# transformer_balancing.net
KiCad netlist of a schematic drawn in EAGLE
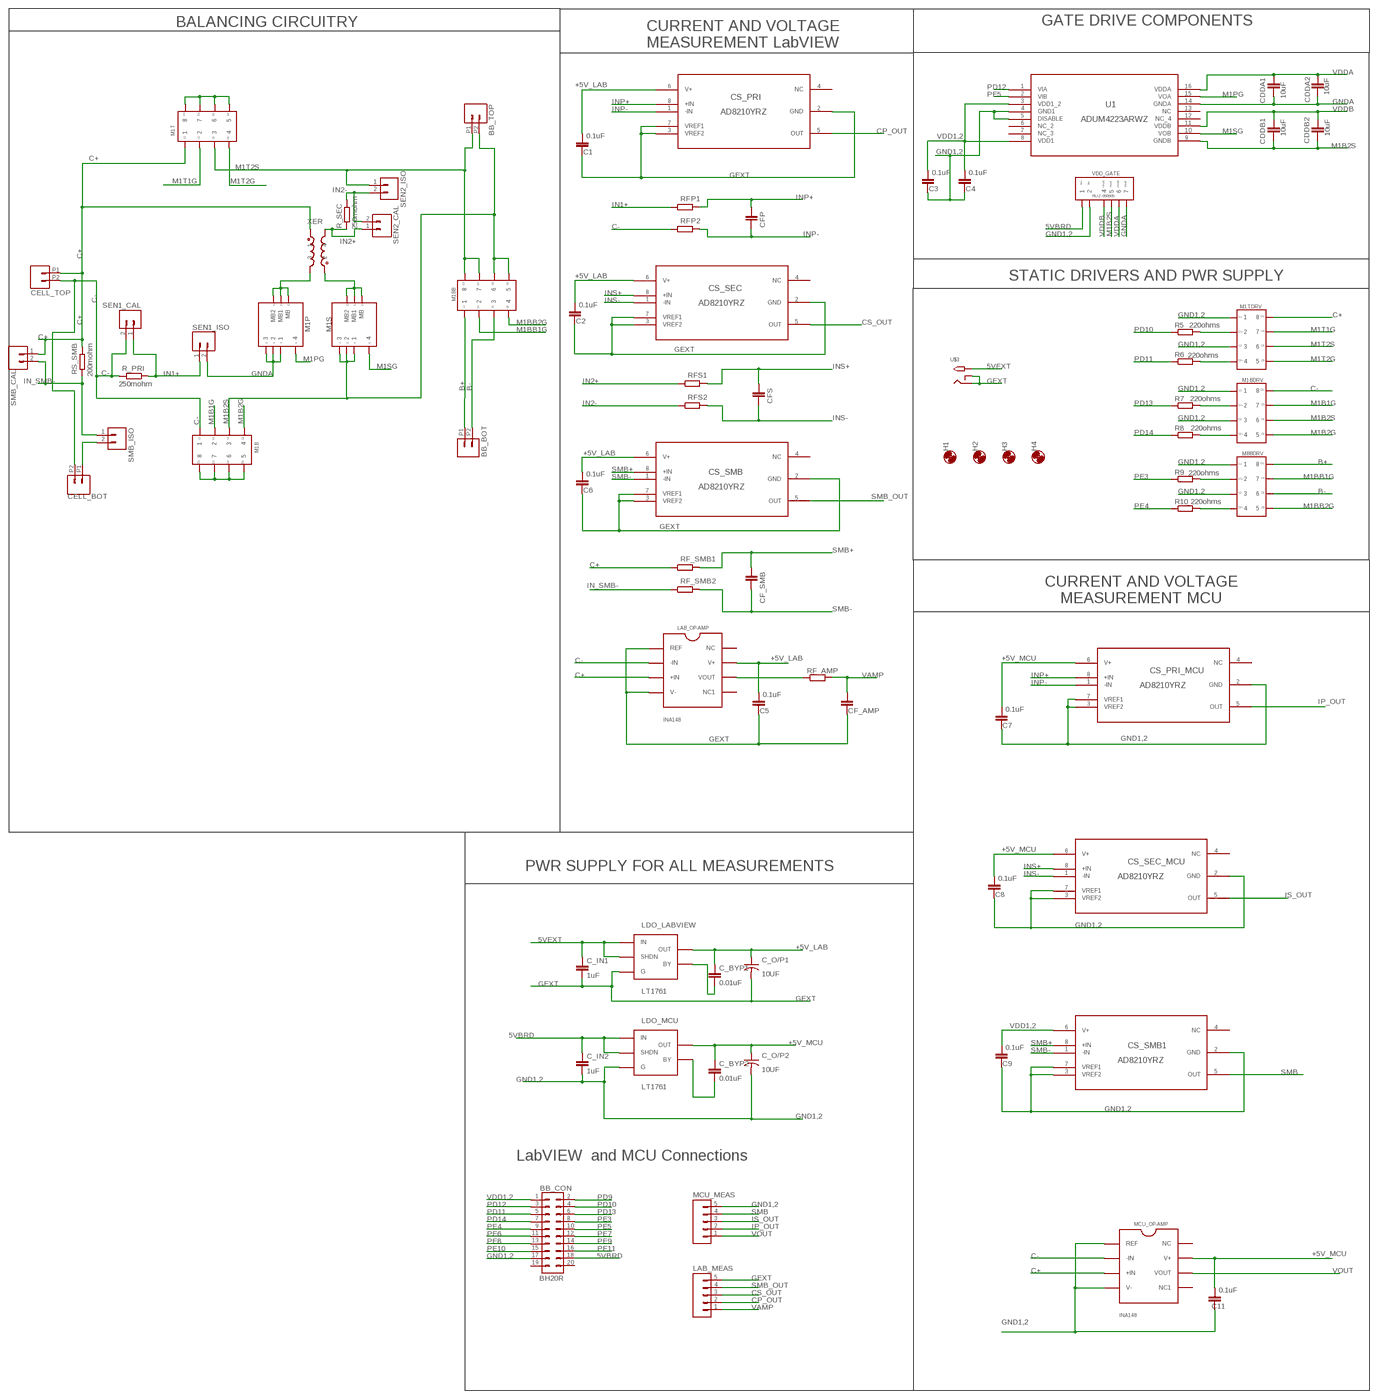
[diagram p0: schematic, sheet 1, overview]
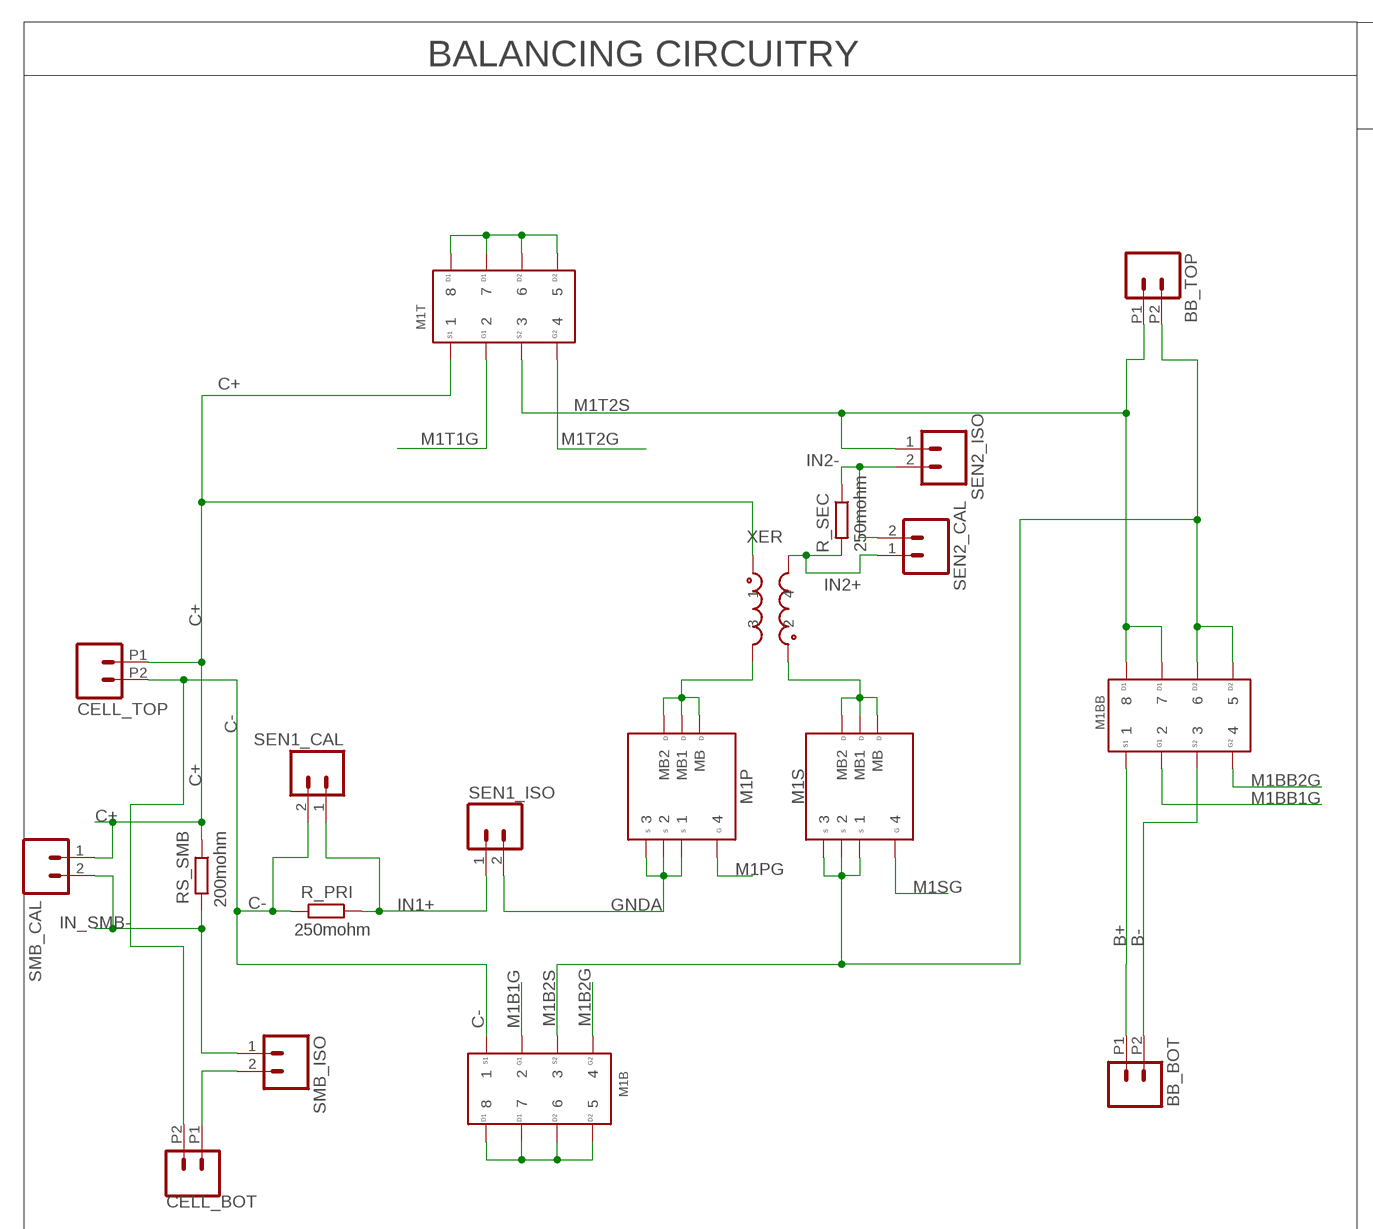
[diagram p1: schematic, sheet 1, part 1 of 4]
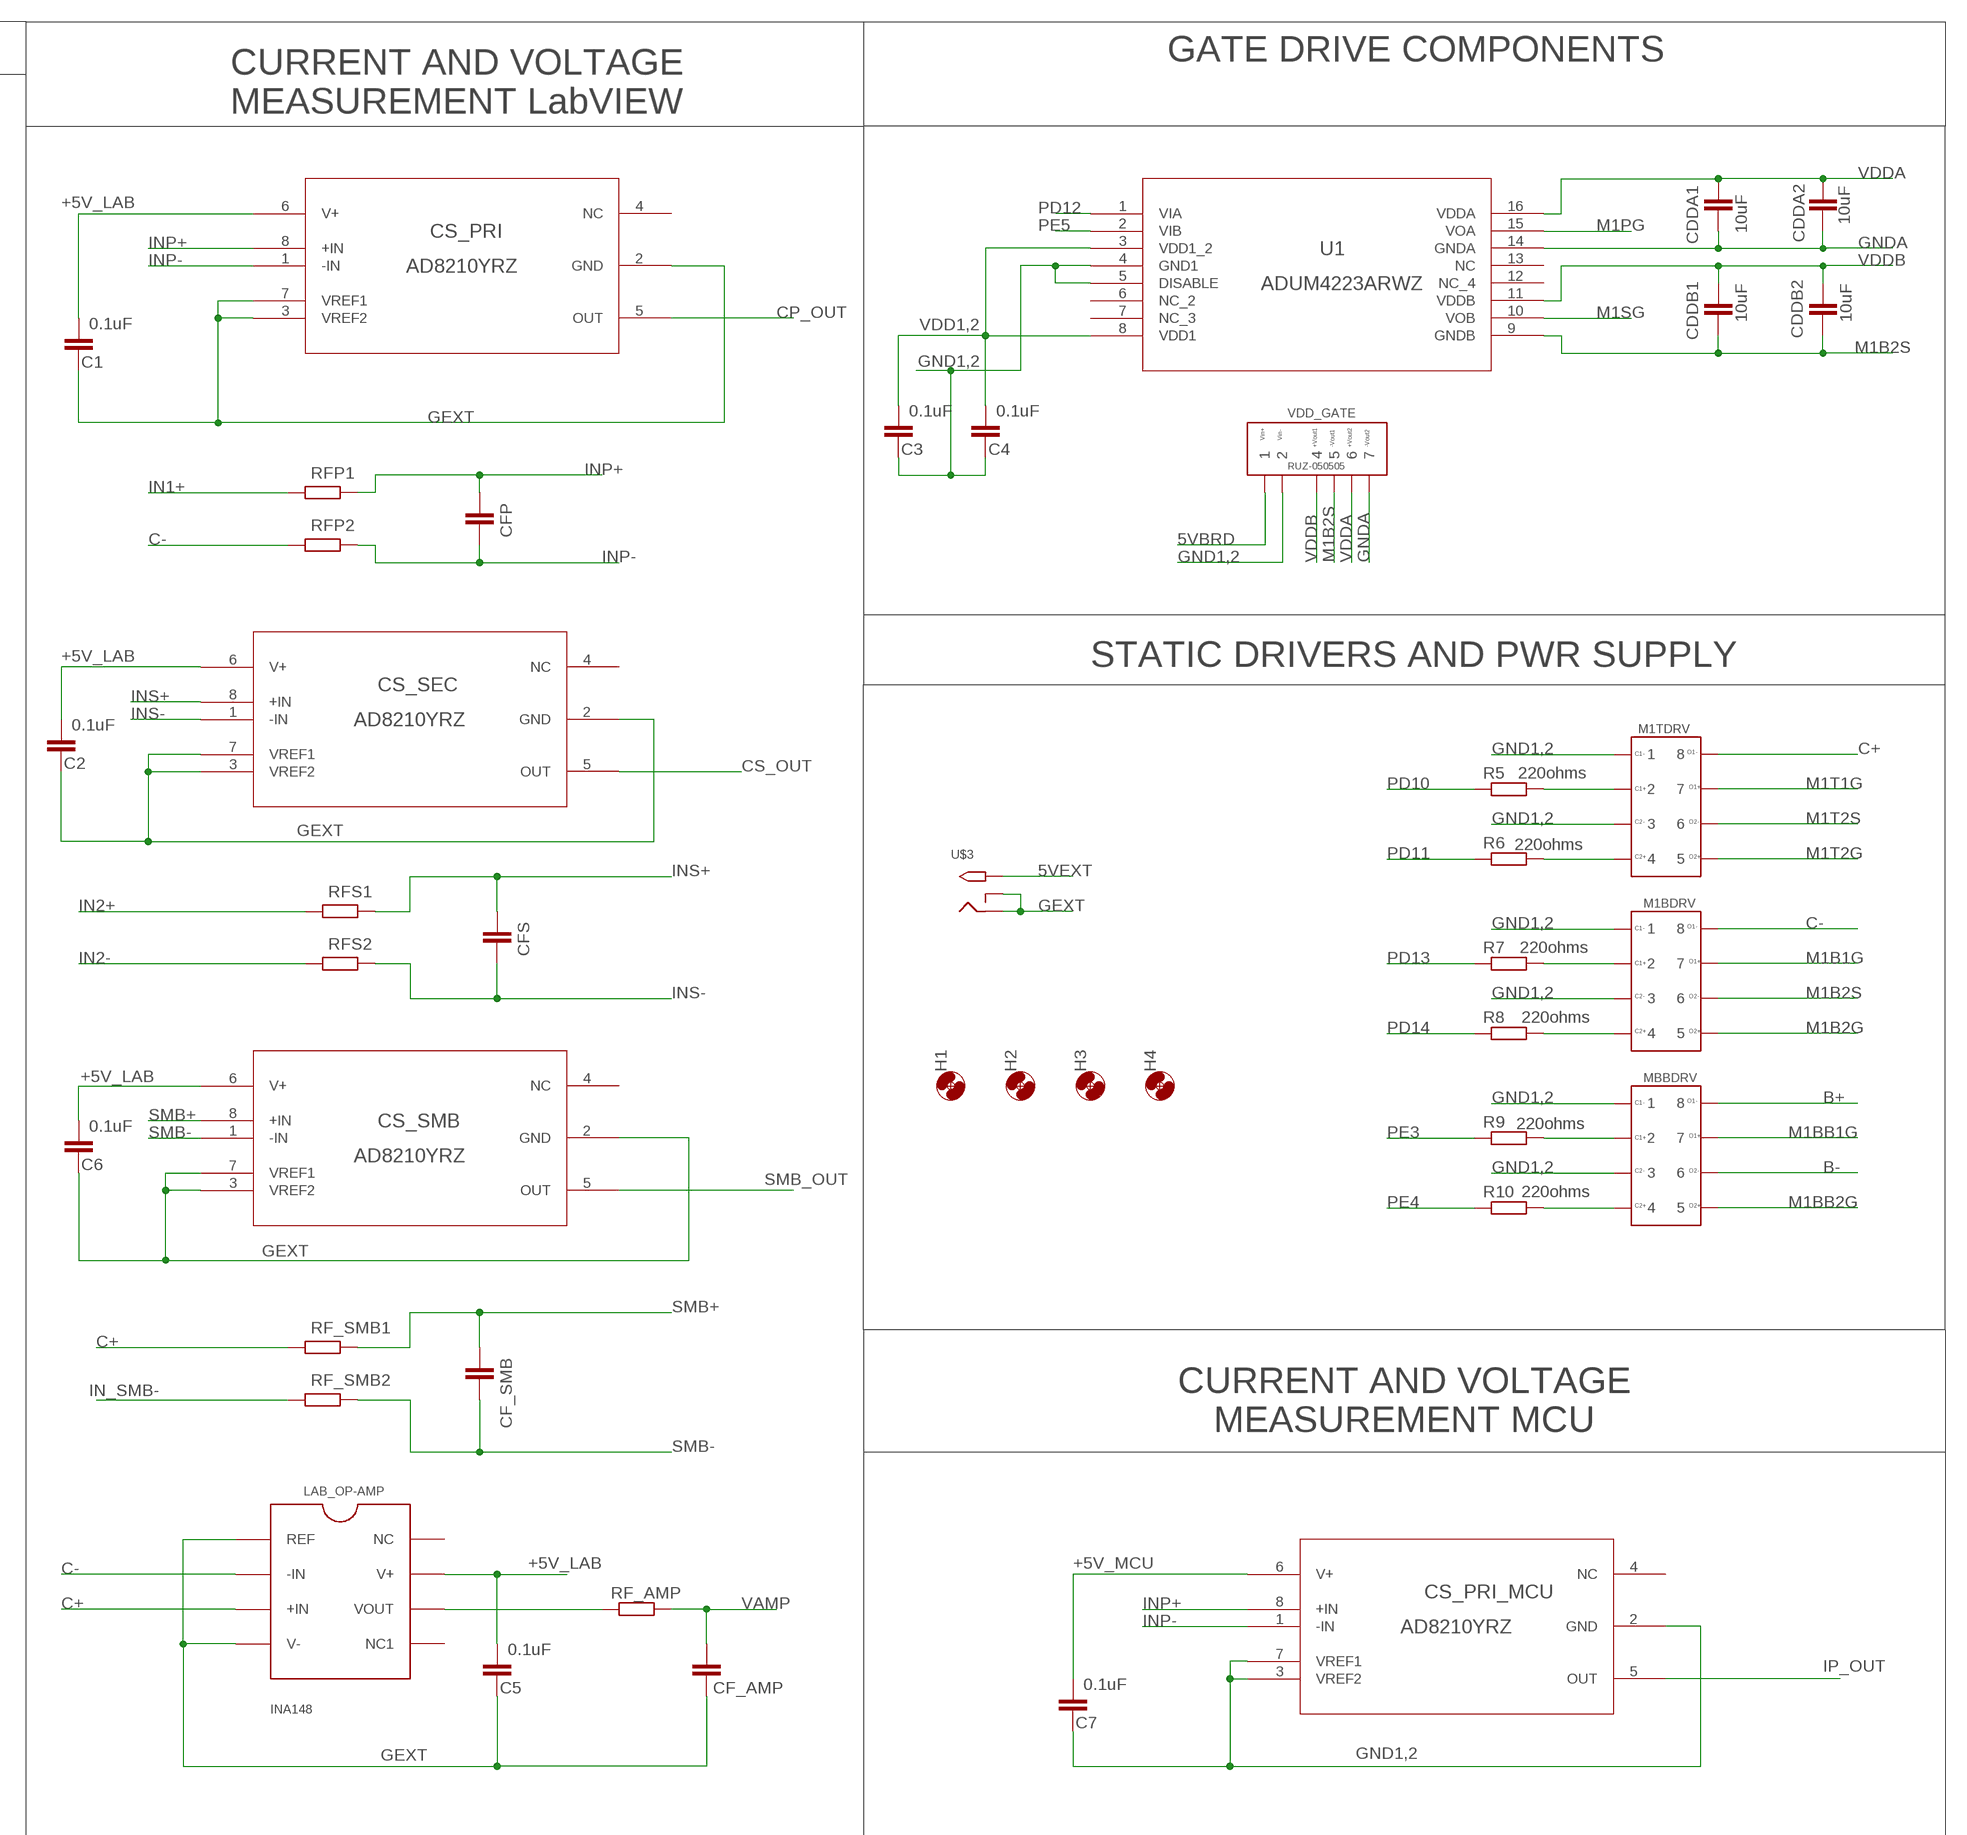
[diagram p2: schematic, sheet 1, part 2 of 4]
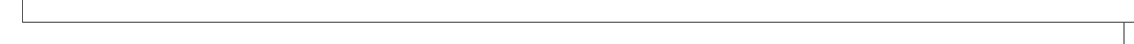
[diagram p3: schematic, sheet 1, part 3 of 4]
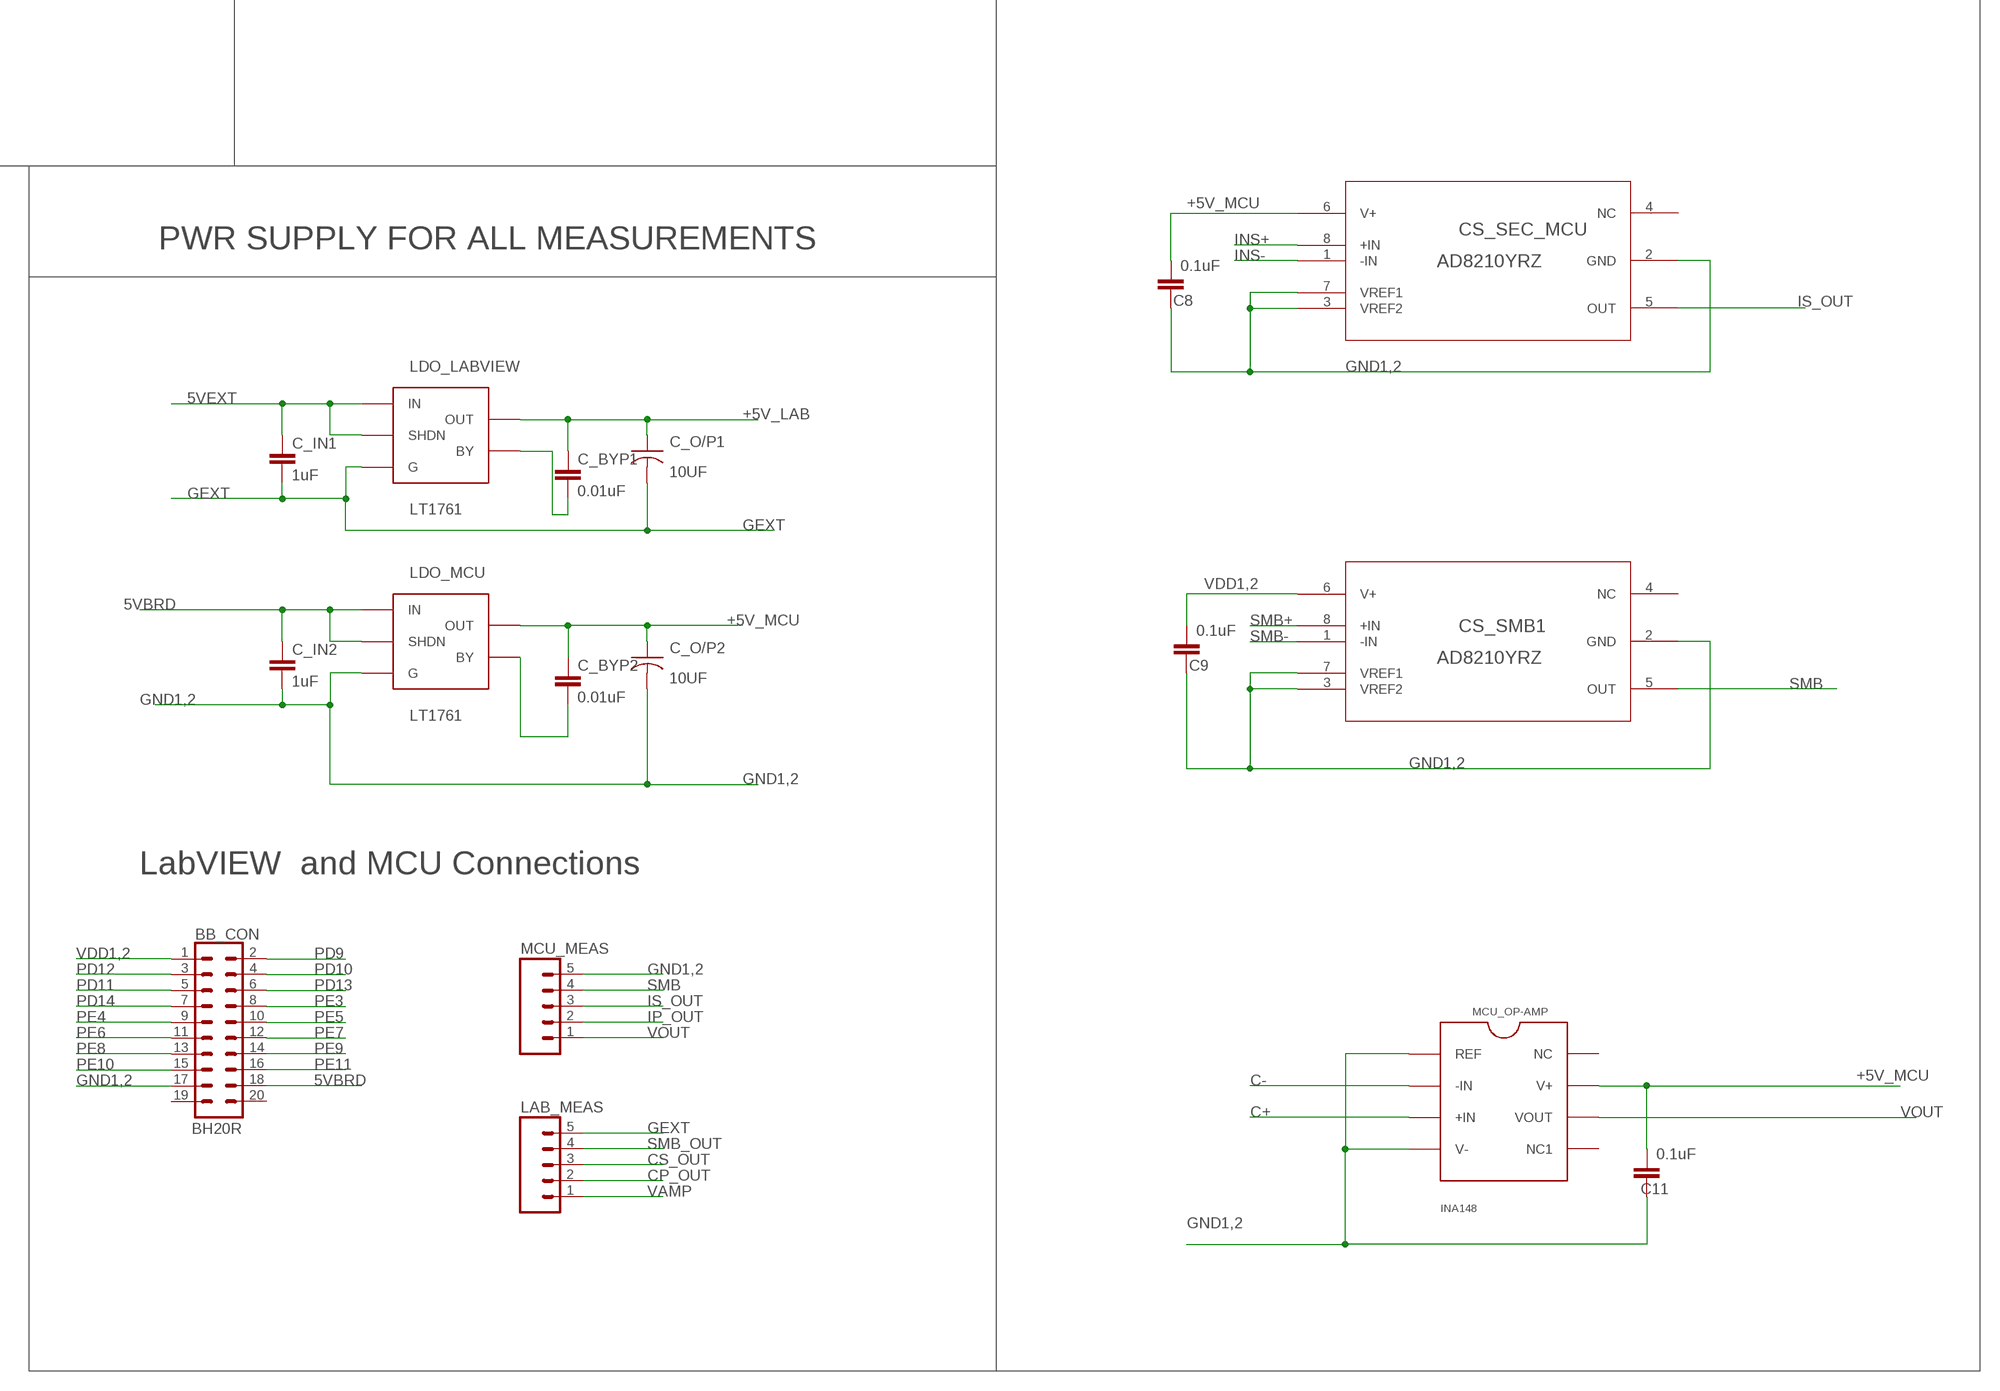
[diagram p4: schematic, sheet 1, part 4 of 4]

(export (version "E")
  (design (tool "Eeschema 10.0.6"))
  (components
    (comp (ref "BB_BOT")
      (value "M022.54MM_SCREWTERM")
      (footprint "eagle-import:1X02_2.54_SCREWTERM")
      (libsource (lib "eagle-import") (part "M022.54MM_SCREWTERM"))
    )
    (comp (ref "BB_CON")
      (value "BH20R")
      (footprint "eagle-import:BH20R")
      (libsource (lib "eagle-import") (part "ML20R"))
    )
    (comp (ref "BB_TOP")
      (value "M022.54MM_SCREWTERM")
      (footprint "eagle-import:1X02_2.54_SCREWTERM")
      (libsource (lib "eagle-import") (part "M022.54MM_SCREWTERM"))
    )
    (comp (ref "C1")
      (value "0.1uF")
      (footprint "eagle-import:C0603")
      (libsource (lib "eagle-import") (part "resistor_C-EUC0603"))
    )
    (comp (ref "C2")
      (value "0.1uF")
      (footprint "eagle-import:C0603")
      (libsource (lib "eagle-import") (part "resistor_C-EUC0603"))
    )
    (comp (ref "C3")
      (value "0.1uF")
      (footprint "eagle-import:C0603")
      (libsource (lib "eagle-import") (part "resistor_C-EUC0603"))
    )
    (comp (ref "C4")
      (value "0.1uF")
      (footprint "eagle-import:C0603")
      (libsource (lib "eagle-import") (part "resistor_C-EUC0603"))
    )
    (comp (ref "C5")
      (value "0.1uF")
      (footprint "eagle-import:C0603")
      (libsource (lib "eagle-import") (part "resistor_C-EUC0603"))
    )
    (comp (ref "C6")
      (value "0.1uF")
      (footprint "eagle-import:C0603")
      (libsource (lib "eagle-import") (part "resistor_C-EUC0603"))
    )
    (comp (ref "C7")
      (value "0.1uF")
      (footprint "eagle-import:C0603")
      (libsource (lib "eagle-import") (part "resistor_C-EUC0603"))
    )
    (comp (ref "C8")
      (value "0.1uF")
      (footprint "eagle-import:C0603")
      (libsource (lib "eagle-import") (part "resistor_C-EUC0603"))
    )
    (comp (ref "C9")
      (value "0.1uF")
      (footprint "eagle-import:C0603")
      (libsource (lib "eagle-import") (part "resistor_C-EUC0603"))
    )
    (comp (ref "C11")
      (value "0.1uF")
      (footprint "eagle-import:C0603")
      (libsource (lib "eagle-import") (part "resistor_C-EUC0603"))
    )
    (comp (ref "CDDA1")
      (value "10uF")
      (footprint "eagle-import:C0603")
      (libsource (lib "eagle-import") (part "resistor_C-EUC0603"))
    )
    (comp (ref "CDDA2")
      (value "10uF")
      (footprint "eagle-import:C0603")
      (libsource (lib "eagle-import") (part "resistor_C-EUC0603"))
    )
    (comp (ref "CDDB1")
      (value "10uF")
      (footprint "eagle-import:C0603")
      (libsource (lib "eagle-import") (part "resistor_C-EUC0603"))
    )
    (comp (ref "CDDB2")
      (value "10uF")
      (footprint "eagle-import:C0603")
      (libsource (lib "eagle-import") (part "resistor_C-EUC0603"))
    )
    (comp (ref "CELL_BOT")
      (value "M022.54MM_SCREWTERM")
      (footprint "eagle-import:1X02_2.54_SCREWTERM")
      (libsource (lib "eagle-import") (part "M022.54MM_SCREWTERM"))
    )
    (comp (ref "CELL_TOP")
      (value "M022.54MM_SCREWTERM")
      (footprint "eagle-import:1X02_2.54_SCREWTERM")
      (libsource (lib "eagle-import") (part "M022.54MM_SCREWTERM"))
    )
    (comp (ref "CFP")
      (value "C-EUC0603")
      (footprint "eagle-import:C0603")
      (libsource (lib "eagle-import") (part "resistor_C-EUC0603"))
    )
    (comp (ref "CFS")
      (value "C-EUC0603")
      (footprint "eagle-import:C0603")
      (libsource (lib "eagle-import") (part "resistor_C-EUC0603"))
    )
    (comp (ref "CF_AMP")
      (value "C-EUC0603")
      (footprint "eagle-import:C0603")
      (libsource (lib "eagle-import") (part "resistor_C-EUC0603"))
    )
    (comp (ref "CF_SMB")
      (value "C-EUC0603")
      (footprint "eagle-import:C0603")
      (libsource (lib "eagle-import") (part "resistor_C-EUC0603"))
    )
    (comp (ref "CS_PRI")
      (value "AD8210YRZ")
      (footprint "eagle-import:R_8")
      (libsource (lib "eagle-import") (part "AD8210YRZ"))
    )
    (comp (ref "CS_PRI_MCU")
      (value "AD8210YRZ")
      (footprint "eagle-import:R_8")
      (libsource (lib "eagle-import") (part "AD8210YRZ"))
    )
    (comp (ref "CS_SEC")
      (value "AD8210YRZ")
      (footprint "eagle-import:R_8")
      (libsource (lib "eagle-import") (part "AD8210YRZ"))
    )
    (comp (ref "CS_SEC_MCU")
      (value "AD8210YRZ")
      (footprint "eagle-import:R_8")
      (libsource (lib "eagle-import") (part "AD8210YRZ"))
    )
    (comp (ref "CS_SMB")
      (value "AD8210YRZ")
      (footprint "eagle-import:R_8")
      (libsource (lib "eagle-import") (part "AD8210YRZ"))
    )
    (comp (ref "CS_SMB1")
      (value "AD8210YRZ")
      (footprint "eagle-import:R_8")
      (libsource (lib "eagle-import") (part "AD8210YRZ"))
    )
    (comp (ref "C_BYP1")
      (value "0.01uF")
      (footprint "eagle-import:C0402")
      (libsource (lib "eagle-import") (part "C-EUC0402"))
    )
    (comp (ref "C_BYP2")
      (value "0.01uF")
      (footprint "eagle-import:C0402")
      (libsource (lib "eagle-import") (part "C-EUC0402"))
    )
    (comp (ref "C_IN1")
      (value "1uF")
      (footprint "eagle-import:C0402")
      (libsource (lib "eagle-import") (part "C-EUC0402"))
    )
    (comp (ref "C_IN2")
      (value "1uF")
      (footprint "eagle-import:C0402")
      (libsource (lib "eagle-import") (part "C-EUC0402"))
    )
    (comp (ref "C_O/P1")
      (value "10UF")
      (footprint "eagle-import:10UF_O_P_CAP_LDO")
      (libsource (lib "eagle-import") (part "10UF_O/P_LDO"))
    )
    (comp (ref "C_O/P2")
      (value "10UF")
      (footprint "eagle-import:10UF_O_P_CAP_LDO")
      (libsource (lib "eagle-import") (part "10UF_O/P_LDO"))
    )
    (comp (ref "H1")
      (value "MOUNT-HOLE3.0")
      (footprint "eagle-import:3,0")
      (libsource (lib "eagle-import") (part "MOUNT-HOLE3.0"))
    )
    (comp (ref "H2")
      (value "MOUNT-HOLE3.0")
      (footprint "eagle-import:3,0")
      (libsource (lib "eagle-import") (part "MOUNT-HOLE3.0"))
    )
    (comp (ref "H3")
      (value "MOUNT-HOLE3.0")
      (footprint "eagle-import:3,0")
      (libsource (lib "eagle-import") (part "MOUNT-HOLE3.0"))
    )
    (comp (ref "H4")
      (value "MOUNT-HOLE3.0")
      (footprint "eagle-import:3,0")
      (libsource (lib "eagle-import") (part "MOUNT-HOLE3.0"))
    )
    (comp (ref "LAB_MEAS")
      (value "M05PTH")
      (footprint "eagle-import:1X05")
      (libsource (lib "eagle-import") (part "M05PTH"))
    )
    (comp (ref "LAB_OP-AMP")
      (value "INA148")
      (footprint "eagle-import:INA148")
      (libsource (lib "eagle-import") (part "INA148"))
    )
    (comp (ref "LDO_LABVIEW")
      (value "LT1761")
      (footprint "eagle-import:LT1761")
      (libsource (lib "eagle-import") (part "LT1761"))
    )
    (comp (ref "LDO_MCU")
      (value "LT1761")
      (footprint "eagle-import:LT1761")
      (libsource (lib "eagle-import") (part "LT1761"))
    )
    (comp (ref "M1B")
      (value "2_CHANNEL_MOSFET")
      (footprint "eagle-import:2_CHANNEL_MOSFET")
      (libsource (lib "eagle-import") (part "2_CHANNEL_MOSFET"))
    )
    (comp (ref "M1BB")
      (value "2_CHANNEL_MOSFET")
      (footprint "eagle-import:2_CHANNEL_MOSFET")
      (libsource (lib "eagle-import") (part "2_CHANNEL_MOSFET"))
    )
    (comp (ref "M1BDRV")
      (value "VOA1263")
      (footprint "eagle-import:VOA1263")
      (libsource (lib "eagle-import") (part "VOA1263"))
    )
    (comp (ref "M1P")
      (value "SWITCHING_MOSFET")
      (footprint "eagle-import:SWITCHING_MOSFET")
      (libsource (lib "eagle-import") (part "SWITCHING_MOSFET"))
    )
    (comp (ref "M1S")
      (value "SWITCHING_MOSFET")
      (footprint "eagle-import:SWITCHING_MOSFET")
      (libsource (lib "eagle-import") (part "SWITCHING_MOSFET"))
    )
    (comp (ref "M1T")
      (value "2_CHANNEL_MOSFET")
      (footprint "eagle-import:2_CHANNEL_MOSFET")
      (libsource (lib "eagle-import") (part "2_CHANNEL_MOSFET"))
    )
    (comp (ref "M1TDRV")
      (value "VOA1263")
      (footprint "eagle-import:VOA1263")
      (libsource (lib "eagle-import") (part "VOA1263"))
    )
    (comp (ref "MBBDRV")
      (value "VOA1263")
      (footprint "eagle-import:VOA1263")
      (libsource (lib "eagle-import") (part "VOA1263"))
    )
    (comp (ref "MCU_MEAS")
      (value "M05PTH")
      (footprint "eagle-import:1X05")
      (libsource (lib "eagle-import") (part "M05PTH"))
    )
    (comp (ref "MCU_OP-AMP")
      (value "INA148")
      (footprint "eagle-import:INA148")
      (libsource (lib "eagle-import") (part "INA148"))
    )
    (comp (ref "R5")
      (value "220ohms")
      (footprint "eagle-import:R0603")
      (libsource (lib "eagle-import") (part "resistor_R-EU_R0603"))
    )
    (comp (ref "R6")
      (value "220ohms")
      (footprint "eagle-import:R0603")
      (libsource (lib "eagle-import") (part "resistor_R-EU_R0603"))
    )
    (comp (ref "R7")
      (value "220ohms")
      (footprint "eagle-import:R0603")
      (libsource (lib "eagle-import") (part "resistor_R-EU_R0603"))
    )
    (comp (ref "R8")
      (value "220ohms")
      (footprint "eagle-import:R0603")
      (libsource (lib "eagle-import") (part "resistor_R-EU_R0603"))
    )
    (comp (ref "R9")
      (value "220ohms")
      (footprint "eagle-import:R0603")
      (libsource (lib "eagle-import") (part "resistor_R-EU_R0603"))
    )
    (comp (ref "R10")
      (value "220ohms")
      (footprint "eagle-import:R0603")
      (libsource (lib "eagle-import") (part "resistor_R-EU_R0603"))
    )
    (comp (ref "RFP1")
      (value "5R")
      (footprint "eagle-import:R0603")
      (libsource (lib "eagle-import") (part "R-EU_R0603"))
    )
    (comp (ref "RFP2")
      (value "5R")
      (footprint "eagle-import:R0603")
      (libsource (lib "eagle-import") (part "R-EU_R0603"))
    )
    (comp (ref "RFS1")
      (value "5R")
      (footprint "eagle-import:R0603")
      (libsource (lib "eagle-import") (part "R-EU_R0603"))
    )
    (comp (ref "RFS2")
      (value "5R")
      (footprint "eagle-import:R0603")
      (libsource (lib "eagle-import") (part "R-EU_R0603"))
    )
    (comp (ref "RF_AMP")
      (value "R-EU_R0603")
      (footprint "eagle-import:R0603")
      (libsource (lib "eagle-import") (part "resistor_R-EU_R0603"))
    )
    (comp (ref "RF_SMB1")
      (value "5R")
      (footprint "eagle-import:R0603")
      (libsource (lib "eagle-import") (part "R-EU_R0603"))
    )
    (comp (ref "RF_SMB2")
      (value "5R")
      (footprint "eagle-import:R0603")
      (libsource (lib "eagle-import") (part "R-EU_R0603"))
    )
    (comp (ref "RS_SMB")
      (value "200mohm")
      (footprint "eagle-import:R0603")
      (libsource (lib "eagle-import") (part "R-EU_R0603"))
    )
    (comp (ref "R_PRI")
      (value "250mohm")
      (footprint "eagle-import:R0603")
      (libsource (lib "eagle-import") (part "R-EU_R0603"))
    )
    (comp (ref "R_SEC")
      (value "250mohm")
      (footprint "eagle-import:R0603")
      (libsource (lib "eagle-import") (part "R-EU_R0603"))
    )
    (comp (ref "SEN1_CAL")
      (value "M02PTH")
      (footprint "eagle-import:1X02")
      (libsource (lib "eagle-import") (part "M02PTH"))
    )
    (comp (ref "SEN1_ISO")
      (value "M02PTH")
      (footprint "eagle-import:1X02")
      (libsource (lib "eagle-import") (part "M02PTH"))
    )
    (comp (ref "SEN2_CAL")
      (value "M02PTH")
      (footprint "eagle-import:1X02")
      (libsource (lib "eagle-import") (part "M02PTH"))
    )
    (comp (ref "SEN2_ISO")
      (value "M02PTH")
      (footprint "eagle-import:1X02")
      (libsource (lib "eagle-import") (part "M02PTH"))
    )
    (comp (ref "SMB_CAL")
      (value "M02PTH")
      (footprint "eagle-import:1X02")
      (libsource (lib "eagle-import") (part "M02PTH"))
    )
    (comp (ref "SMB_ISO")
      (value "M02PTH")
      (footprint "eagle-import:1X02")
      (libsource (lib "eagle-import") (part "M02PTH"))
    )
    (comp (ref "U$3")
      (value "2.1MMJACK")
      (footprint "eagle-import:PJ-102A")
      (libsource (lib "eagle-import") (part "2.1MMJACK"))
    )
    (comp (ref "U1")
      (value "ADUM4223ARWZ")
      (footprint "eagle-import:RW_16")
      (libsource (lib "eagle-import") (part "ADUM4223ARWZ"))
    )
    (comp (ref "VDD_GATE")
      (value "RUZ-050505")
      (footprint "eagle-import:RUZ-050505")
      (libsource (lib "eagle-import") (part "RUZ-050505"))
    )
    (comp (ref "XER")
      (value "COUPLED_INDUCTOR")
      (footprint "eagle-import:COUPLED_INDUCTOR")
      (libsource (lib "eagle-import") (part "COUPLED_INDUCTOR"))
    )
  )
  (nets
    (net (code "1") (name "/+5V_LAB") (class "Default")
      (node (ref "C1") (pin "1") (pinfunction "1_1") (pintype "passive"))
      (node (ref "C2") (pin "1") (pinfunction "1_1") (pintype "passive"))
      (node (ref "C5") (pin "1") (pinfunction "1_1") (pintype "passive"))
      (node (ref "C6") (pin "1") (pinfunction "1_1") (pintype "passive"))
      (node (ref "CS_PRI") (pin "6") (pinfunction "V+_6") (pintype "passive"))
      (node (ref "CS_SEC") (pin "6") (pinfunction "V+_6") (pintype "passive"))
      (node (ref "CS_SMB") (pin "6") (pinfunction "V+_6") (pintype "passive"))
      (node (ref "C_BYP1") (pin "1") (pinfunction "1_1") (pintype "passive"))
      (node (ref "C_O/P1") (pin "1") (pinfunction "3_1") (pintype "passive"))
      (node (ref "LAB_OP-AMP") (pin "V+") (pinfunction "V+_V+") (pintype "bidirectional"))
      (node (ref "LDO_LABVIEW") (pin "5") (pinfunction "OUT_5") (pintype "bidirectional"))
    )
    (net (code "2") (name "/+5V_MCU") (class "Default")
      (node (ref "C11") (pin "1") (pinfunction "1_1") (pintype "passive"))
      (node (ref "C7") (pin "1") (pinfunction "1_1") (pintype "passive"))
      (node (ref "C8") (pin "1") (pinfunction "1_1") (pintype "passive"))
      (node (ref "CS_PRI_MCU") (pin "6") (pinfunction "V+_6") (pintype "passive"))
      (node (ref "CS_SEC_MCU") (pin "6") (pinfunction "V+_6") (pintype "passive"))
      (node (ref "C_BYP2") (pin "1") (pinfunction "1_1") (pintype "passive"))
      (node (ref "C_O/P2") (pin "1") (pinfunction "3_1") (pintype "passive"))
      (node (ref "LDO_MCU") (pin "5") (pinfunction "OUT_5") (pintype "bidirectional"))
      (node (ref "MCU_OP-AMP") (pin "V+") (pinfunction "V+_V+") (pintype "bidirectional"))
    )
    (net (code "3") (name "/5VBRD") (class "Default")
      (node (ref "BB_CON") (pin "18") (pinfunction "18_18") (pintype "passive"))
      (node (ref "C_IN2") (pin "1") (pinfunction "1_1") (pintype "passive"))
      (node (ref "LDO_MCU") (pin "1") (pinfunction "IN_1") (pintype "bidirectional"))
      (node (ref "LDO_MCU") (pin "3") (pinfunction "SHDN_3") (pintype "bidirectional"))
      (node (ref "VDD_GATE") (pin "1") (pinfunction "1_1") (pintype "bidirectional"))
    )
    (net (code "4") (name "/5VEXT") (class "Default")
      (node (ref "C_IN1") (pin "1") (pinfunction "1_1") (pintype "passive"))
      (node (ref "LDO_LABVIEW") (pin "1") (pinfunction "IN_1") (pintype "bidirectional"))
      (node (ref "LDO_LABVIEW") (pin "3") (pinfunction "SHDN_3") (pintype "bidirectional"))
      (node (ref "U$3") (pin "TIP") (pinfunction "TIP_TIP") (pintype "bidirectional"))
    )
    (net (code "5") (name "/B+") (class "Default")
      (node (ref "BB_BOT") (pin "P1") (pinfunction "1_P1") (pintype "passive"))
      (node (ref "M1BB") (pin "1") (pinfunction "1_1") (pintype "passive"))
      (node (ref "MBBDRV") (pin "8") (pinfunction "8_8") (pintype "bidirectional"))
    )
    (net (code "6") (name "/B-") (class "Default")
      (node (ref "BB_BOT") (pin "P2") (pinfunction "2_P2") (pintype "passive"))
      (node (ref "M1BB") (pin "3") (pinfunction "3_3") (pintype "passive"))
      (node (ref "MBBDRV") (pin "6") (pinfunction "6_6") (pintype "bidirectional"))
    )
    (net (code "7") (name "/C+") (class "Default")
      (node (ref "CELL_TOP") (pin "P1") (pinfunction "1_P1") (pintype "passive"))
      (node (ref "LAB_OP-AMP") (pin "+IN") (pinfunction "+IN_+IN") (pintype "bidirectional"))
      (node (ref "M1T") (pin "1") (pinfunction "1_1") (pintype "passive"))
      (node (ref "M1TDRV") (pin "8") (pinfunction "8_8") (pintype "bidirectional"))
      (node (ref "MCU_OP-AMP") (pin "+IN") (pinfunction "+IN_+IN") (pintype "bidirectional"))
      (node (ref "RF_SMB1") (pin "1") (pinfunction "1_1") (pintype "passive"))
      (node (ref "RS_SMB") (pin "1") (pinfunction "1_1") (pintype "passive"))
      (node (ref "SMB_CAL") (pin "1") (pinfunction "1_1") (pintype "passive"))
      (node (ref "XER") (pin "1") (pinfunction "1_1") (pintype "passive"))
    )
    (net (code "8") (name "/C-") (class "Default")
      (node (ref "CELL_BOT") (pin "P2") (pinfunction "2_P2") (pintype "passive"))
      (node (ref "CELL_TOP") (pin "P2") (pinfunction "2_P2") (pintype "passive"))
      (node (ref "LAB_OP-AMP") (pin "-IN") (pinfunction "-IN_-IN") (pintype "bidirectional"))
      (node (ref "M1B") (pin "1") (pinfunction "1_1") (pintype "passive"))
      (node (ref "M1BDRV") (pin "8") (pinfunction "8_8") (pintype "bidirectional"))
      (node (ref "MCU_OP-AMP") (pin "-IN") (pinfunction "-IN_-IN") (pintype "bidirectional"))
      (node (ref "RFP2") (pin "1") (pinfunction "1_1") (pintype "passive"))
      (node (ref "R_PRI") (pin "2") (pinfunction "2_2") (pintype "passive"))
      (node (ref "SEN1_CAL") (pin "2") (pinfunction "2_2") (pintype "passive"))
    )
    (net (code "9") (name "/CP_OUT") (class "Default")
      (node (ref "CS_PRI") (pin "5") (pinfunction "OUT_5") (pintype "passive"))
      (node (ref "LAB_MEAS") (pin "2") (pinfunction "2_2") (pintype "passive"))
    )
    (net (code "10") (name "/CS_OUT") (class "Default")
      (node (ref "CS_SEC") (pin "5") (pinfunction "OUT_5") (pintype "passive"))
      (node (ref "LAB_MEAS") (pin "3") (pinfunction "3_3") (pintype "passive"))
    )
    (net (code "11") (name "/GEXT") (class "Default")
      (node (ref "C1") (pin "2") (pinfunction "2_2") (pintype "passive"))
      (node (ref "C2") (pin "2") (pinfunction "2_2") (pintype "passive"))
      (node (ref "C5") (pin "2") (pinfunction "2_2") (pintype "passive"))
      (node (ref "C6") (pin "2") (pinfunction "2_2") (pintype "passive"))
      (node (ref "CF_AMP") (pin "2") (pinfunction "2_2") (pintype "passive"))
      (node (ref "CS_PRI") (pin "2") (pinfunction "GND_2") (pintype "passive"))
      (node (ref "CS_PRI") (pin "3") (pinfunction "VREF2_3") (pintype "passive"))
      (node (ref "CS_PRI") (pin "7") (pinfunction "VREF1_7") (pintype "passive"))
      (node (ref "CS_SEC") (pin "2") (pinfunction "GND_2") (pintype "passive"))
      (node (ref "CS_SEC") (pin "3") (pinfunction "VREF2_3") (pintype "passive"))
      (node (ref "CS_SEC") (pin "7") (pinfunction "VREF1_7") (pintype "passive"))
      (node (ref "CS_SMB") (pin "2") (pinfunction "GND_2") (pintype "passive"))
      (node (ref "CS_SMB") (pin "3") (pinfunction "VREF2_3") (pintype "passive"))
      (node (ref "CS_SMB") (pin "7") (pinfunction "VREF1_7") (pintype "passive"))
      (node (ref "C_IN1") (pin "2") (pinfunction "2_2") (pintype "passive"))
      (node (ref "C_O/P1") (pin "2") (pinfunction "4_2") (pintype "passive"))
      (node (ref "LAB_MEAS") (pin "5") (pinfunction "5_5") (pintype "passive"))
      (node (ref "LAB_OP-AMP") (pin "REF") (pinfunction "REF_REF") (pintype "bidirectional"))
      (node (ref "LAB_OP-AMP") (pin "V-") (pinfunction "V-_V-") (pintype "bidirectional"))
      (node (ref "LDO_LABVIEW") (pin "2") (pinfunction "G_2") (pintype "bidirectional"))
      (node (ref "U$3") (pin "RING") (pinfunction "RING_RING") (pintype "bidirectional"))
      (node (ref "U$3") (pin "RING_SW") (pinfunction "RING_SW_RING_SW") (pintype "bidirectional"))
    )
    (net (code "12") (name "/GND1,2") (class "Default")
      (node (ref "BB_CON") (pin "17") (pinfunction "17_17") (pintype "passive"))
      (node (ref "C11") (pin "2") (pinfunction "2_2") (pintype "passive"))
      (node (ref "C3") (pin "2") (pinfunction "2_2") (pintype "passive"))
      (node (ref "C4") (pin "2") (pinfunction "2_2") (pintype "passive"))
      (node (ref "C7") (pin "2") (pinfunction "2_2") (pintype "passive"))
      (node (ref "C8") (pin "2") (pinfunction "2_2") (pintype "passive"))
      (node (ref "C9") (pin "2") (pinfunction "2_2") (pintype "passive"))
      (node (ref "CS_PRI_MCU") (pin "2") (pinfunction "GND_2") (pintype "passive"))
      (node (ref "CS_PRI_MCU") (pin "3") (pinfunction "VREF2_3") (pintype "passive"))
      (node (ref "CS_PRI_MCU") (pin "7") (pinfunction "VREF1_7") (pintype "passive"))
      (node (ref "CS_SEC_MCU") (pin "2") (pinfunction "GND_2") (pintype "passive"))
      (node (ref "CS_SEC_MCU") (pin "3") (pinfunction "VREF2_3") (pintype "passive"))
      (node (ref "CS_SEC_MCU") (pin "7") (pinfunction "VREF1_7") (pintype "passive"))
      (node (ref "CS_SMB1") (pin "2") (pinfunction "GND_2") (pintype "passive"))
      (node (ref "CS_SMB1") (pin "3") (pinfunction "VREF2_3") (pintype "passive"))
      (node (ref "CS_SMB1") (pin "7") (pinfunction "VREF1_7") (pintype "passive"))
      (node (ref "C_IN2") (pin "2") (pinfunction "2_2") (pintype "passive"))
      (node (ref "C_O/P2") (pin "2") (pinfunction "4_2") (pintype "passive"))
      (node (ref "LDO_MCU") (pin "2") (pinfunction "G_2") (pintype "bidirectional"))
      (node (ref "M1BDRV") (pin "1") (pinfunction "1_1") (pintype "bidirectional"))
      (node (ref "M1BDRV") (pin "3") (pinfunction "3_3") (pintype "bidirectional"))
      (node (ref "M1TDRV") (pin "1") (pinfunction "1_1") (pintype "bidirectional"))
      (node (ref "M1TDRV") (pin "3") (pinfunction "3_3") (pintype "bidirectional"))
      (node (ref "MBBDRV") (pin "1") (pinfunction "1_1") (pintype "bidirectional"))
      (node (ref "MBBDRV") (pin "3") (pinfunction "3_3") (pintype "bidirectional"))
      (node (ref "MCU_MEAS") (pin "5") (pinfunction "5_5") (pintype "passive"))
      (node (ref "MCU_OP-AMP") (pin "REF") (pinfunction "REF_REF") (pintype "bidirectional"))
      (node (ref "MCU_OP-AMP") (pin "V-") (pinfunction "V-_V-") (pintype "bidirectional"))
      (node (ref "U1") (pin "4") (pinfunction "GND1_4") (pintype "passive"))
      (node (ref "U1") (pin "5") (pinfunction "DISABLE_5") (pintype "passive"))
      (node (ref "VDD_GATE") (pin "2") (pinfunction "2_2") (pintype "bidirectional"))
    )
    (net (code "13") (name "/GNDA") (class "Default")
      (node (ref "CDDA1") (pin "2") (pinfunction "2_2") (pintype "passive"))
      (node (ref "CDDA2") (pin "2") (pinfunction "2_2") (pintype "passive"))
      (node (ref "M1P") (pin "1") (pinfunction "1_1") (pintype "bidirectional"))
      (node (ref "M1P") (pin "2") (pinfunction "2_2") (pintype "bidirectional"))
      (node (ref "M1P") (pin "3") (pinfunction "3_3") (pintype "bidirectional"))
      (node (ref "SEN1_ISO") (pin "2") (pinfunction "2_2") (pintype "passive"))
      (node (ref "U1") (pin "14") (pinfunction "GNDA_14") (pintype "passive"))
      (node (ref "VDD_GATE") (pin "7") (pinfunction "7_7") (pintype "bidirectional"))
    )
    (net (code "14") (name "/IN1+") (class "Default")
      (node (ref "RFP1") (pin "1") (pinfunction "1_1") (pintype "passive"))
      (node (ref "R_PRI") (pin "1") (pinfunction "1_1") (pintype "passive"))
      (node (ref "SEN1_CAL") (pin "1") (pinfunction "1_1") (pintype "passive"))
      (node (ref "SEN1_ISO") (pin "1") (pinfunction "1_1") (pintype "passive"))
    )
    (net (code "15") (name "/IN2+") (class "Default")
      (node (ref "RFS1") (pin "1") (pinfunction "1_1") (pintype "passive"))
      (node (ref "R_SEC") (pin "2") (pinfunction "2_2") (pintype "passive"))
      (node (ref "SEN2_CAL") (pin "1") (pinfunction "1_1") (pintype "passive"))
      (node (ref "XER") (pin "4") (pinfunction "4_4") (pintype "passive"))
    )
    (net (code "16") (name "/IN2-") (class "Default")
      (node (ref "RFS2") (pin "1") (pinfunction "1_1") (pintype "passive"))
      (node (ref "R_SEC") (pin "1") (pinfunction "1_1") (pintype "passive"))
      (node (ref "SEN2_CAL") (pin "2") (pinfunction "2_2") (pintype "passive"))
      (node (ref "SEN2_ISO") (pin "2") (pinfunction "2_2") (pintype "passive"))
    )
    (net (code "17") (name "/INP+") (class "Default")
      (node (ref "CFP") (pin "1") (pinfunction "1_1") (pintype "passive"))
      (node (ref "CS_PRI") (pin "8") (pinfunction "+IN_8") (pintype "passive"))
      (node (ref "CS_PRI_MCU") (pin "8") (pinfunction "+IN_8") (pintype "passive"))
      (node (ref "RFP1") (pin "2") (pinfunction "2_2") (pintype "passive"))
    )
    (net (code "18") (name "/INP-") (class "Default")
      (node (ref "CFP") (pin "2") (pinfunction "2_2") (pintype "passive"))
      (node (ref "CS_PRI") (pin "1") (pinfunction "-IN_1") (pintype "passive"))
      (node (ref "CS_PRI_MCU") (pin "1") (pinfunction "-IN_1") (pintype "passive"))
      (node (ref "RFP2") (pin "2") (pinfunction "2_2") (pintype "passive"))
    )
    (net (code "19") (name "/INS+") (class "Default")
      (node (ref "CFS") (pin "1") (pinfunction "1_1") (pintype "passive"))
      (node (ref "CS_SEC") (pin "8") (pinfunction "+IN_8") (pintype "passive"))
      (node (ref "CS_SEC_MCU") (pin "8") (pinfunction "+IN_8") (pintype "passive"))
      (node (ref "RFS1") (pin "2") (pinfunction "2_2") (pintype "passive"))
    )
    (net (code "20") (name "/INS-") (class "Default")
      (node (ref "CFS") (pin "2") (pinfunction "2_2") (pintype "passive"))
      (node (ref "CS_SEC") (pin "1") (pinfunction "-IN_1") (pintype "passive"))
      (node (ref "CS_SEC_MCU") (pin "1") (pinfunction "-IN_1") (pintype "passive"))
      (node (ref "RFS2") (pin "2") (pinfunction "2_2") (pintype "passive"))
    )
    (net (code "21") (name "/IN_SMB-") (class "Default")
      (node (ref "RF_SMB2") (pin "1") (pinfunction "1_1") (pintype "passive"))
      (node (ref "RS_SMB") (pin "2") (pinfunction "2_2") (pintype "passive"))
      (node (ref "SMB_CAL") (pin "2") (pinfunction "2_2") (pintype "passive"))
      (node (ref "SMB_ISO") (pin "1") (pinfunction "1_1") (pintype "passive"))
    )
    (net (code "22") (name "/IP_OUT") (class "Default")
      (node (ref "CS_PRI_MCU") (pin "5") (pinfunction "OUT_5") (pintype "passive"))
      (node (ref "MCU_MEAS") (pin "2") (pinfunction "2_2") (pintype "passive"))
    )
    (net (code "23") (name "/IS_OUT") (class "Default")
      (node (ref "CS_SEC_MCU") (pin "5") (pinfunction "OUT_5") (pintype "passive"))
      (node (ref "MCU_MEAS") (pin "3") (pinfunction "3_3") (pintype "passive"))
    )
    (net (code "24") (name "/M1B1G") (class "Default")
      (node (ref "M1B") (pin "2") (pinfunction "2_2") (pintype "passive"))
      (node (ref "M1BDRV") (pin "7") (pinfunction "7_7") (pintype "bidirectional"))
    )
    (net (code "25") (name "/M1B2G") (class "Default")
      (node (ref "M1B") (pin "4") (pinfunction "4_4") (pintype "passive"))
      (node (ref "M1BDRV") (pin "5") (pinfunction "5_5") (pintype "bidirectional"))
    )
    (net (code "26") (name "/M1B2S") (class "Default")
      (node (ref "BB_TOP") (pin "P2") (pinfunction "2_P2") (pintype "passive"))
      (node (ref "CDDB1") (pin "2") (pinfunction "2_2") (pintype "passive"))
      (node (ref "CDDB2") (pin "2") (pinfunction "2_2") (pintype "passive"))
      (node (ref "M1B") (pin "3") (pinfunction "3_3") (pintype "passive"))
      (node (ref "M1BB") (pin "5") (pinfunction "5_5") (pintype "passive"))
      (node (ref "M1BB") (pin "6") (pinfunction "6_6") (pintype "passive"))
      (node (ref "M1BDRV") (pin "6") (pinfunction "6_6") (pintype "bidirectional"))
      (node (ref "M1S") (pin "1") (pinfunction "1_1") (pintype "bidirectional"))
      (node (ref "M1S") (pin "2") (pinfunction "2_2") (pintype "bidirectional"))
      (node (ref "M1S") (pin "3") (pinfunction "3_3") (pintype "bidirectional"))
      (node (ref "U1") (pin "9") (pinfunction "GNDB_9") (pintype "passive"))
      (node (ref "VDD_GATE") (pin "5") (pinfunction "5_5") (pintype "bidirectional"))
    )
    (net (code "27") (name "/M1BB1G") (class "Default")
      (node (ref "M1BB") (pin "2") (pinfunction "2_2") (pintype "passive"))
      (node (ref "MBBDRV") (pin "7") (pinfunction "7_7") (pintype "bidirectional"))
    )
    (net (code "28") (name "/M1BB2G") (class "Default")
      (node (ref "M1BB") (pin "4") (pinfunction "4_4") (pintype "passive"))
      (node (ref "MBBDRV") (pin "5") (pinfunction "5_5") (pintype "bidirectional"))
    )
    (net (code "29") (name "/M1PG") (class "Default")
      (node (ref "M1P") (pin "4") (pinfunction "4_4") (pintype "bidirectional"))
      (node (ref "U1") (pin "15") (pinfunction "VOA_15") (pintype "passive"))
    )
    (net (code "30") (name "/M1SG") (class "Default")
      (node (ref "M1S") (pin "4") (pinfunction "4_4") (pintype "bidirectional"))
      (node (ref "U1") (pin "10") (pinfunction "VOB_10") (pintype "passive"))
    )
    (net (code "31") (name "/M1T1G") (class "Default")
      (node (ref "M1T") (pin "2") (pinfunction "2_2") (pintype "passive"))
      (node (ref "M1TDRV") (pin "7") (pinfunction "7_7") (pintype "bidirectional"))
    )
    (net (code "32") (name "/M1T2G") (class "Default")
      (node (ref "M1T") (pin "4") (pinfunction "4_4") (pintype "passive"))
      (node (ref "M1TDRV") (pin "5") (pinfunction "5_5") (pintype "bidirectional"))
    )
    (net (code "33") (name "/M1T2S") (class "Default")
      (node (ref "BB_TOP") (pin "P1") (pinfunction "1_P1") (pintype "passive"))
      (node (ref "M1BB") (pin "7") (pinfunction "7_7") (pintype "passive"))
      (node (ref "M1BB") (pin "8") (pinfunction "8_8") (pintype "passive"))
      (node (ref "M1T") (pin "3") (pinfunction "3_3") (pintype "passive"))
      (node (ref "M1TDRV") (pin "6") (pinfunction "6_6") (pintype "bidirectional"))
      (node (ref "SEN2_ISO") (pin "1") (pinfunction "1_1") (pintype "passive"))
    )
    (net (code "34") (name "/PD9") (class "Default")
      (node (ref "BB_CON") (pin "2") (pinfunction "2_2") (pintype "passive"))
    )
    (net (code "35") (name "/PD10") (class "Default")
      (node (ref "BB_CON") (pin "4") (pinfunction "4_4") (pintype "passive"))
      (node (ref "R5") (pin "1") (pinfunction "1_1") (pintype "passive"))
    )
    (net (code "36") (name "/PD11") (class "Default")
      (node (ref "BB_CON") (pin "5") (pinfunction "5_5") (pintype "passive"))
      (node (ref "R6") (pin "1") (pinfunction "1_1") (pintype "passive"))
    )
    (net (code "37") (name "/PD12") (class "Default")
      (node (ref "BB_CON") (pin "3") (pinfunction "3_3") (pintype "passive"))
      (node (ref "U1") (pin "1") (pinfunction "VIA_1") (pintype "passive"))
    )
    (net (code "38") (name "/PD13") (class "Default")
      (node (ref "BB_CON") (pin "6") (pinfunction "6_6") (pintype "passive"))
      (node (ref "R7") (pin "1") (pinfunction "1_1") (pintype "passive"))
    )
    (net (code "39") (name "/PD14") (class "Default")
      (node (ref "BB_CON") (pin "7") (pinfunction "7_7") (pintype "passive"))
      (node (ref "R8") (pin "1") (pinfunction "1_1") (pintype "passive"))
    )
    (net (code "40") (name "/PE3") (class "Default")
      (node (ref "BB_CON") (pin "8") (pinfunction "8_8") (pintype "passive"))
      (node (ref "R9") (pin "1") (pinfunction "1_1") (pintype "passive"))
    )
    (net (code "41") (name "/PE4") (class "Default")
      (node (ref "BB_CON") (pin "9") (pinfunction "9_9") (pintype "passive"))
      (node (ref "R10") (pin "1") (pinfunction "1_1") (pintype "passive"))
    )
    (net (code "42") (name "/PE5") (class "Default")
      (node (ref "BB_CON") (pin "10") (pinfunction "10_10") (pintype "passive"))
      (node (ref "U1") (pin "2") (pinfunction "VIB_2") (pintype "passive"))
    )
    (net (code "43") (name "/PE6") (class "Default")
      (node (ref "BB_CON") (pin "11") (pinfunction "11_11") (pintype "passive"))
    )
    (net (code "44") (name "/PE7") (class "Default")
      (node (ref "BB_CON") (pin "12") (pinfunction "12_12") (pintype "passive"))
    )
    (net (code "45") (name "/PE8") (class "Default")
      (node (ref "BB_CON") (pin "13") (pinfunction "13_13") (pintype "passive"))
    )
    (net (code "46") (name "/PE9") (class "Default")
      (node (ref "BB_CON") (pin "14") (pinfunction "14_14") (pintype "passive"))
    )
    (net (code "47") (name "/PE10") (class "Default")
      (node (ref "BB_CON") (pin "15") (pinfunction "15_15") (pintype "passive"))
    )
    (net (code "48") (name "/PE11") (class "Default")
      (node (ref "BB_CON") (pin "16") (pinfunction "16_16") (pintype "passive"))
    )
    (net (code "49") (name "/SMB") (class "Default")
      (node (ref "CS_SMB1") (pin "5") (pinfunction "OUT_5") (pintype "passive"))
      (node (ref "MCU_MEAS") (pin "4") (pinfunction "4_4") (pintype "passive"))
    )
    (net (code "50") (name "/SMB+") (class "Default")
      (node (ref "CF_SMB") (pin "1") (pinfunction "1_1") (pintype "passive"))
      (node (ref "CS_SMB") (pin "8") (pinfunction "+IN_8") (pintype "passive"))
      (node (ref "CS_SMB1") (pin "8") (pinfunction "+IN_8") (pintype "passive"))
      (node (ref "RF_SMB1") (pin "2") (pinfunction "2_2") (pintype "passive"))
    )
    (net (code "51") (name "/SMB-") (class "Default")
      (node (ref "CF_SMB") (pin "2") (pinfunction "2_2") (pintype "passive"))
      (node (ref "CS_SMB") (pin "1") (pinfunction "-IN_1") (pintype "passive"))
      (node (ref "CS_SMB1") (pin "1") (pinfunction "-IN_1") (pintype "passive"))
      (node (ref "RF_SMB2") (pin "2") (pinfunction "2_2") (pintype "passive"))
    )
    (net (code "52") (name "/SMB_OUT") (class "Default")
      (node (ref "CS_SMB") (pin "5") (pinfunction "OUT_5") (pintype "passive"))
      (node (ref "LAB_MEAS") (pin "4") (pinfunction "4_4") (pintype "passive"))
    )
    (net (code "53") (name "/VAMP") (class "Default")
      (node (ref "CF_AMP") (pin "1") (pinfunction "1_1") (pintype "passive"))
      (node (ref "LAB_MEAS") (pin "1") (pinfunction "1_1") (pintype "passive"))
      (node (ref "RF_AMP") (pin "2") (pinfunction "2_2") (pintype "passive"))
    )
    (net (code "54") (name "/VDD1,2") (class "Default")
      (node (ref "BB_CON") (pin "1") (pinfunction "1_1") (pintype "passive"))
      (node (ref "C3") (pin "1") (pinfunction "1_1") (pintype "passive"))
      (node (ref "C4") (pin "1") (pinfunction "1_1") (pintype "passive"))
      (node (ref "C9") (pin "1") (pinfunction "1_1") (pintype "passive"))
      (node (ref "CS_SMB1") (pin "6") (pinfunction "V+_6") (pintype "passive"))
      (node (ref "U1") (pin "3") (pinfunction "VDD1_2_3") (pintype "passive"))
      (node (ref "U1") (pin "8") (pinfunction "VDD1_8") (pintype "passive"))
    )
    (net (code "55") (name "/VDDA") (class "Default")
      (node (ref "CDDA1") (pin "1") (pinfunction "1_1") (pintype "passive"))
      (node (ref "CDDA2") (pin "1") (pinfunction "1_1") (pintype "passive"))
      (node (ref "U1") (pin "16") (pinfunction "VDDA_16") (pintype "passive"))
      (node (ref "VDD_GATE") (pin "6") (pinfunction "6_6") (pintype "bidirectional"))
    )
    (net (code "56") (name "/VDDB") (class "Default")
      (node (ref "CDDB1") (pin "1") (pinfunction "1_1") (pintype "passive"))
      (node (ref "CDDB2") (pin "1") (pinfunction "1_1") (pintype "passive"))
      (node (ref "U1") (pin "11") (pinfunction "VDDB_11") (pintype "passive"))
      (node (ref "VDD_GATE") (pin "4") (pinfunction "4_4") (pintype "bidirectional"))
    )
    (net (code "57") (name "/VOUT") (class "Default")
      (node (ref "MCU_MEAS") (pin "1") (pinfunction "1_1") (pintype "passive"))
      (node (ref "MCU_OP-AMP") (pin "VOUT") (pinfunction "VOUT_VOUT") (pintype "bidirectional"))
    )
    (net (code "58") (name "Net-(CELL_BOT-1)") (class "Default")
      (node (ref "CELL_BOT") (pin "P1") (pinfunction "1_P1") (pintype "passive"))
      (node (ref "SMB_ISO") (pin "2") (pinfunction "2_2") (pintype "passive"))
    )
    (net (code "59") (name "Net-(LAB_OP-AMP-PadVOUT)") (class "Default")
      (node (ref "LAB_OP-AMP") (pin "VOUT") (pinfunction "VOUT_VOUT") (pintype "bidirectional"))
      (node (ref "RF_AMP") (pin "1") (pinfunction "1_1") (pintype "passive"))
    )
    (net (code "60") (name "Net-(LDO_LABVIEW-BY)") (class "Default")
      (node (ref "C_BYP1") (pin "2") (pinfunction "2_2") (pintype "passive"))
      (node (ref "LDO_LABVIEW") (pin "4") (pinfunction "BY_4") (pintype "bidirectional"))
    )
    (net (code "61") (name "Net-(LDO_MCU-BY)") (class "Default")
      (node (ref "C_BYP2") (pin "2") (pinfunction "2_2") (pintype "passive"))
      (node (ref "LDO_MCU") (pin "4") (pinfunction "BY_4") (pintype "bidirectional"))
    )
    (net (code "62") (name "Net-(M1B-Pad5)") (class "Default")
      (node (ref "M1B") (pin "5") (pinfunction "5_5") (pintype "passive"))
      (node (ref "M1B") (pin "6") (pinfunction "6_6") (pintype "passive"))
      (node (ref "M1B") (pin "7") (pinfunction "7_7") (pintype "passive"))
      (node (ref "M1B") (pin "8") (pinfunction "8_8") (pintype "passive"))
    )
    (net (code "63") (name "Net-(M1BDRV-Pad2)") (class "Default")
      (node (ref "M1BDRV") (pin "2") (pinfunction "2_2") (pintype "bidirectional"))
      (node (ref "R7") (pin "2") (pinfunction "2_2") (pintype "passive"))
    )
    (net (code "64") (name "Net-(M1BDRV-Pad4)") (class "Default")
      (node (ref "M1BDRV") (pin "4") (pinfunction "4_4") (pintype "bidirectional"))
      (node (ref "R8") (pin "2") (pinfunction "2_2") (pintype "passive"))
    )
    (net (code "65") (name "Net-(M1P-PadMB)") (class "Default")
      (node (ref "M1P") (pin "MB") (pinfunction "MB_MB") (pintype "bidirectional"))
      (node (ref "M1P") (pin "MB1") (pinfunction "MB1_MB1") (pintype "bidirectional"))
      (node (ref "M1P") (pin "MB2") (pinfunction "MB2_MB2") (pintype "bidirectional"))
      (node (ref "XER") (pin "3") (pinfunction "3_3") (pintype "passive"))
    )
    (net (code "66") (name "Net-(M1S-PadMB)") (class "Default")
      (node (ref "M1S") (pin "MB") (pinfunction "MB_MB") (pintype "bidirectional"))
      (node (ref "M1S") (pin "MB1") (pinfunction "MB1_MB1") (pintype "bidirectional"))
      (node (ref "M1S") (pin "MB2") (pinfunction "MB2_MB2") (pintype "bidirectional"))
      (node (ref "XER") (pin "2") (pinfunction "2_2") (pintype "passive"))
    )
    (net (code "67") (name "Net-(M1T-Pad5)") (class "Default")
      (node (ref "M1T") (pin "5") (pinfunction "5_5") (pintype "passive"))
      (node (ref "M1T") (pin "6") (pinfunction "6_6") (pintype "passive"))
      (node (ref "M1T") (pin "7") (pinfunction "7_7") (pintype "passive"))
      (node (ref "M1T") (pin "8") (pinfunction "8_8") (pintype "passive"))
    )
    (net (code "68") (name "Net-(M1TDRV-Pad2)") (class "Default")
      (node (ref "M1TDRV") (pin "2") (pinfunction "2_2") (pintype "bidirectional"))
      (node (ref "R5") (pin "2") (pinfunction "2_2") (pintype "passive"))
    )
    (net (code "69") (name "Net-(M1TDRV-Pad4)") (class "Default")
      (node (ref "M1TDRV") (pin "4") (pinfunction "4_4") (pintype "bidirectional"))
      (node (ref "R6") (pin "2") (pinfunction "2_2") (pintype "passive"))
    )
    (net (code "70") (name "Net-(MBBDRV-Pad2)") (class "Default")
      (node (ref "MBBDRV") (pin "2") (pinfunction "2_2") (pintype "bidirectional"))
      (node (ref "R9") (pin "2") (pinfunction "2_2") (pintype "passive"))
    )
    (net (code "71") (name "Net-(MBBDRV-Pad4)") (class "Default")
      (node (ref "MBBDRV") (pin "4") (pinfunction "4_4") (pintype "bidirectional"))
      (node (ref "R10") (pin "2") (pinfunction "2_2") (pintype "passive"))
    )
    (net (code "72") (name "unconnected-(BB_CON-Pad19)") (class "Default")
      (node (ref "BB_CON") (pin "19") (pinfunction "19_19") (pintype "passive"))
    )
    (net (code "73") (name "unconnected-(BB_CON-Pad20)") (class "Default")
      (node (ref "BB_CON") (pin "20") (pinfunction "20_20") (pintype "passive"))
    )
    (net (code "74") (name "unconnected-(CS_PRI-NC-Pad4)") (class "Default")
      (node (ref "CS_PRI") (pin "4") (pinfunction "NC_4") (pintype "passive"))
    )
    (net (code "75") (name "unconnected-(CS_PRI_MCU-NC-Pad4)") (class "Default")
      (node (ref "CS_PRI_MCU") (pin "4") (pinfunction "NC_4") (pintype "passive"))
    )
    (net (code "76") (name "unconnected-(CS_SEC-NC-Pad4)") (class "Default")
      (node (ref "CS_SEC") (pin "4") (pinfunction "NC_4") (pintype "passive"))
    )
    (net (code "77") (name "unconnected-(CS_SEC_MCU-NC-Pad4)") (class "Default")
      (node (ref "CS_SEC_MCU") (pin "4") (pinfunction "NC_4") (pintype "passive"))
    )
    (net (code "78") (name "unconnected-(CS_SMB-NC-Pad4)") (class "Default")
      (node (ref "CS_SMB") (pin "4") (pinfunction "NC_4") (pintype "passive"))
    )
    (net (code "79") (name "unconnected-(CS_SMB1-NC-Pad4)") (class "Default")
      (node (ref "CS_SMB1") (pin "4") (pinfunction "NC_4") (pintype "passive"))
    )
    (net (code "80") (name "unconnected-(LAB_OP-AMP-PadNC)") (class "Default")
      (node (ref "LAB_OP-AMP") (pin "NC") (pinfunction "NC_NC") (pintype "bidirectional"))
    )
    (net (code "81") (name "unconnected-(LAB_OP-AMP-PadNC1)") (class "Default")
      (node (ref "LAB_OP-AMP") (pin "NC1") (pinfunction "NC1_NC1") (pintype "bidirectional"))
    )
    (net (code "82") (name "unconnected-(MCU_OP-AMP-PadNC)") (class "Default")
      (node (ref "MCU_OP-AMP") (pin "NC") (pinfunction "NC_NC") (pintype "bidirectional"))
    )
    (net (code "83") (name "unconnected-(MCU_OP-AMP-PadNC1)") (class "Default")
      (node (ref "MCU_OP-AMP") (pin "NC1") (pinfunction "NC1_NC1") (pintype "bidirectional"))
    )
    (net (code "84") (name "unconnected-(U1-NC-Pad13)") (class "Default")
      (node (ref "U1") (pin "13") (pinfunction "NC_13") (pintype "passive"))
    )
    (net (code "85") (name "unconnected-(U1-NC_2-Pad6)") (class "Default")
      (node (ref "U1") (pin "6") (pinfunction "NC_2_6") (pintype "passive"))
    )
    (net (code "86") (name "unconnected-(U1-NC_3-Pad7)") (class "Default")
      (node (ref "U1") (pin "7") (pinfunction "NC_3_7") (pintype "passive"))
    )
    (net (code "87") (name "unconnected-(U1-NC_4-Pad12)") (class "Default")
      (node (ref "U1") (pin "12") (pinfunction "NC_4_12") (pintype "passive"))
    )
  )
)
